# Current_Measurement.net
KiCad netlist of a schematic drawn in Altium Designer
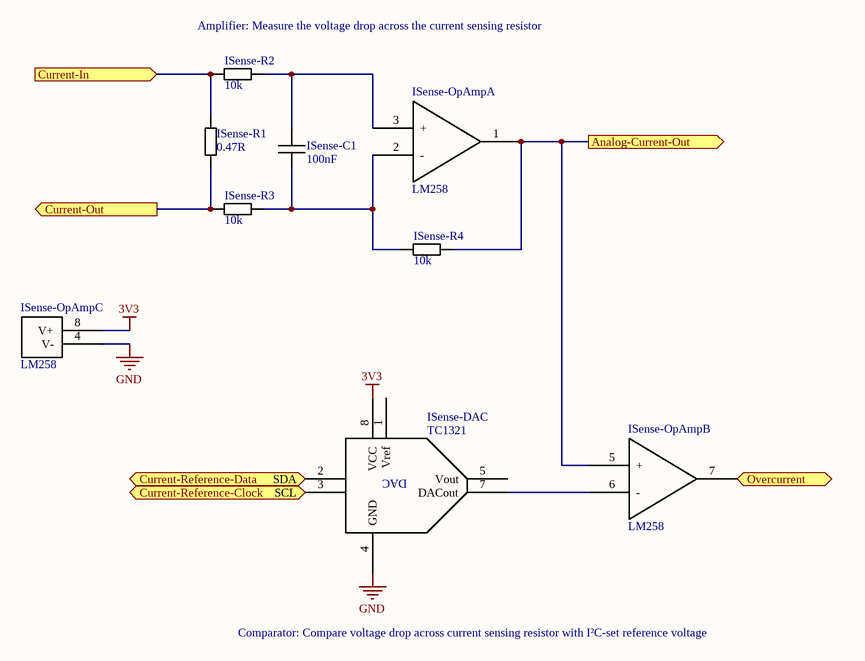
[diagram p0: Current Measurement.SchDoc]

(export (version "E")
  (design (tool "Eeschema 10.0.6"))
  (components
    (comp (ref "ISense-C1")
      (value "100nF")
      (footprint "C 0805 / 2012")
      (libsource (lib "Standard") (part "Capacitor"))
    )
    (comp (ref "ISense-DAC")
      (value "TC1321")
      (footprint "SOIC-8")
      (description "DAC 10-Bit Two-Wire")
      (libsource (lib "ICs") (part "TC1321"))
    )
    (comp (ref "ISense-OpAmp")
      (value "LM258")
      (footprint "SOIC-8")
      (description "Dual OpAmp")
      (libsource (lib "ICs") (part "LM258"))
    )
    (comp (ref "ISense-R1")
      (value "0.47R")
      (footprint "R 0805 / 2012")
      (libsource (lib "Standard") (part "Resistor"))
    )
    (comp (ref "ISense-R2")
      (value "10k")
      (footprint "R 0805 / 2012")
      (libsource (lib "") (part "Resistor_1"))
    )
    (comp (ref "ISense-R3")
      (value "10k")
      (footprint "R 0805 / 2012")
      (libsource (lib "") (part "Resistor_1"))
    )
    (comp (ref "ISense-R4")
      (value "10k")
      (footprint "R 0805 / 2012")
      (libsource (lib "") (part "Resistor_1"))
    )
  )
  (nets
    (net (code "1") (name "/Analog-Current-Out") (class "Default")
      (node (ref "ISense-OpAmp") (pin "1") (pinfunction "OUT_1") (pintype "passive"))
      (node (ref "ISense-OpAmp") (pin "5") (pinfunction "+_5") (pintype "passive"))
      (node (ref "ISense-R4") (pin "2") (pinfunction "2_2") (pintype "passive"))
    )
    (net (code "2") (name "/Current-In") (class "Default")
      (node (ref "ISense-R1") (pin "2") (pinfunction "2_2") (pintype "passive"))
      (node (ref "ISense-R2") (pin "1") (pinfunction "1_1") (pintype "passive"))
    )
    (net (code "3") (name "/Current-Out") (class "Default")
      (node (ref "ISense-R1") (pin "1") (pinfunction "1_1") (pintype "passive"))
      (node (ref "ISense-R3") (pin "1") (pinfunction "1_1") (pintype "passive"))
    )
    (net (code "6") (name "/Overcurrent") (class "Default")
      (node (ref "ISense-OpAmp") (pin "7") (pinfunction "OUT_7") (pintype "passive"))
    )
    (net (code "7") (name "3V3") (class "Default")
      (node (ref "ISense-DAC") (pin "8") (pinfunction "VCC_8") (pintype "passive"))
      (node (ref "ISense-OpAmp") (pin "8") (pinfunction "V+_8") (pintype "passive"))
    )
    (net (code "8") (name "GND") (class "Default")
      (node (ref "ISense-DAC") (pin "4") (pinfunction "GND_4") (pintype "passive"))
      (node (ref "ISense-OpAmp") (pin "4") (pinfunction "V-_4") (pintype "passive"))
    )
    (net (code "9") (name "Net-(ISense-DAC-DACout)") (class "Default")
      (node (ref "ISense-DAC") (pin "7") (pinfunction "DACout_7") (pintype "passive"))
      (node (ref "ISense-OpAmp") (pin "6") (pinfunction "-_6") (pintype "passive"))
    )
    (net (code "10") (name "Net-(ISense-OpAmpA-+)") (class "Default")
      (node (ref "ISense-C1") (pin "1") (pinfunction "1_1") (pintype "passive"))
      (node (ref "ISense-OpAmp") (pin "3") (pinfunction "+_3") (pintype "passive"))
      (node (ref "ISense-R2") (pin "2") (pinfunction "2_2") (pintype "passive"))
    )
    (net (code "11") (name "Net-(ISense-OpAmpA--)") (class "Default")
      (node (ref "ISense-C1") (pin "2") (pinfunction "1_2") (pintype "passive"))
      (node (ref "ISense-OpAmp") (pin "2") (pinfunction "-_2") (pintype "passive"))
      (node (ref "ISense-R3") (pin "2") (pinfunction "2_2") (pintype "passive"))
      (node (ref "ISense-R4") (pin "1") (pinfunction "1_1") (pintype "passive"))
    )
    (net (code "12") (name "unconnected-(ISense-DAC-SCL-Pad3)") (class "Default")
      (node (ref "ISense-DAC") (pin "3") (pinfunction "SCL_3") (pintype "passive"))
    )
    (net (code "13") (name "unconnected-(ISense-DAC-SDA-Pad2)") (class "Default")
      (node (ref "ISense-DAC") (pin "2") (pinfunction "SDA_2") (pintype "passive"))
    )
    (net (code "14") (name "unconnected-(ISense-DAC-Vout-Pad5)") (class "Default")
      (node (ref "ISense-DAC") (pin "5") (pinfunction "Vout_5") (pintype "passive"))
    )
    (net (code "15") (name "unconnected-(ISense-DAC-Vref-Pad1)") (class "Default")
      (node (ref "ISense-DAC") (pin "1") (pinfunction "Vref_1") (pintype "passive"))
    )
  )
)
